# NG2092_SD_Card.net
KiCad netlist of a schematic drawn in Altium Designer
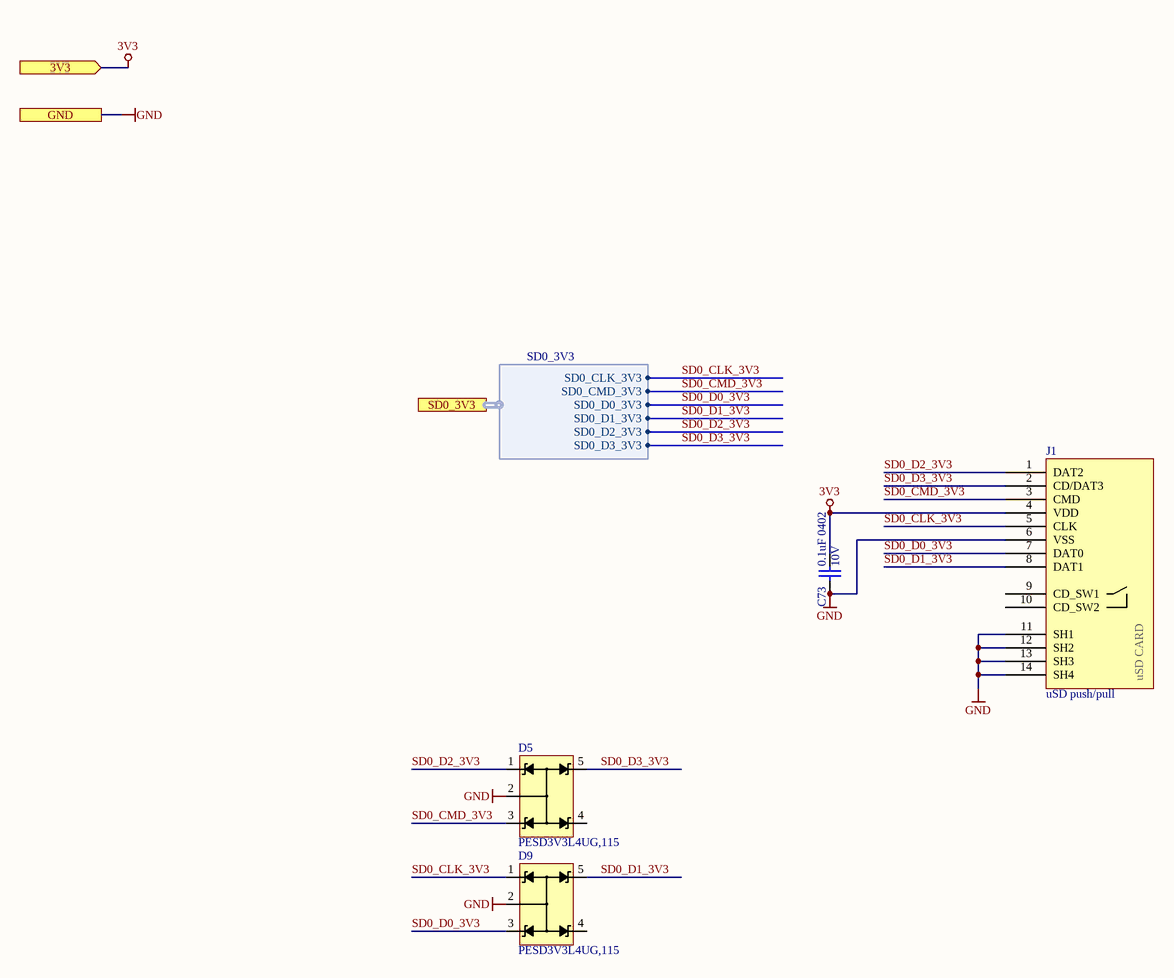
[diagram p0: NG2092_SD_Card.SchDoc]

(export (version "E")
  (design (tool "Eeschema 10.0.6"))
  (components
    (comp (ref "C73")
      (value "0.1uF 0402")
      (footprint "CAP_Altium_Vault_Generic:CAPC0402(1005)70_L")
      (description "CAP CER 0.1UF 10V X7R 0402 5%")
      (fields (field (name "TOLERANCE") "5%") (field (name "VOLTAGE RATING") "10V"))
      (libsource (lib "LuxonisMaster") (part "GRM155R71A104JA01D"))
    )
    (comp (ref "D5")
      (value "PESD3V3L4UG,115")
      (footprint "PESD3V3L4UG,115")
      (description "TVS DIODE 3V3 8V 5TSSOP")
      (libsource (lib "NG2092") (part "PESD3V3L4UG,115"))
    )
    (comp (ref "D9")
      (value "PESD3V3L4UG,115")
      (footprint "PESD3V3L4UG,115")
      (description "TVS DIODE 3V3 8V 5TSSOP")
      (libsource (lib "NG2092") (part "PESD3V3L4UG,115"))
    )
    (comp (ref "J1")
      (value "uSD push/pull")
      (footprint "LuxonisMaster:104031-0811")
      (description "CONN MICRO SD CARD PUSH-PULL R/A")
      (libsource (lib "LuxonisMaster") (part "104031-0811"))
    )
  )
  (nets
    (net (code "2") (name "/SD0_CLK_3V3") (class "Default")
      (node (ref "D9") (pin "1") (pinfunction "1_1") (pintype "passive"))
      (node (ref "J1") (pin "5") (pinfunction "CLK_5") (pintype "passive"))
    )
    (net (code "3") (name "/SD0_CMD_3V3") (class "Default")
      (node (ref "D5") (pin "3") (pinfunction "3_3") (pintype "passive"))
      (node (ref "J1") (pin "3") (pinfunction "CMD_3") (pintype "passive"))
    )
    (net (code "4") (name "/SD0_D0_3V3") (class "Default")
      (node (ref "D9") (pin "3") (pinfunction "3_3") (pintype "passive"))
      (node (ref "J1") (pin "7") (pinfunction "DAT0_7") (pintype "passive"))
    )
    (net (code "5") (name "/SD0_D1_3V3") (class "Default")
      (node (ref "D9") (pin "5") (pinfunction "5_5") (pintype "passive"))
      (node (ref "J1") (pin "8") (pinfunction "DAT1_8") (pintype "passive"))
    )
    (net (code "6") (name "/SD0_D2_3V3") (class "Default")
      (node (ref "D5") (pin "1") (pinfunction "1_1") (pintype "passive"))
      (node (ref "J1") (pin "1") (pinfunction "DAT2_1") (pintype "passive"))
    )
    (net (code "7") (name "/SD0_D3_3V3") (class "Default")
      (node (ref "D5") (pin "5") (pinfunction "5_5") (pintype "passive"))
      (node (ref "J1") (pin "2") (pinfunction "CD/DAT3_2") (pintype "passive"))
    )
    (net (code "9") (name "3V3") (class "Default")
      (node (ref "C73") (pin "2") (pinfunction "2_2") (pintype "passive"))
      (node (ref "J1") (pin "4") (pinfunction "VDD_4") (pintype "passive"))
    )
    (net (code "10") (name "GND") (class "Default")
      (node (ref "C73") (pin "1") (pinfunction "1_1") (pintype "passive"))
      (node (ref "D5") (pin "2") (pinfunction "2_2") (pintype "passive"))
      (node (ref "D9") (pin "2") (pinfunction "2_2") (pintype "passive"))
      (node (ref "J1") (pin "11") (pinfunction "SH1_11") (pintype "passive"))
      (node (ref "J1") (pin "12") (pinfunction "SH2_12") (pintype "passive"))
      (node (ref "J1") (pin "13") (pinfunction "SH3_13") (pintype "passive"))
      (node (ref "J1") (pin "14") (pinfunction "SH4_14") (pintype "passive"))
      (node (ref "J1") (pin "6") (pinfunction "VSS_6") (pintype "passive"))
    )
    (net (code "11") (name "unconnected-(D5-Pad4)") (class "Default")
      (node (ref "D5") (pin "4") (pinfunction "4_4") (pintype "passive"))
    )
    (net (code "12") (name "unconnected-(D9-Pad4)") (class "Default")
      (node (ref "D9") (pin "4") (pinfunction "4_4") (pintype "passive"))
    )
    (net (code "13") (name "unconnected-(J1-CD_SW1-Pad9)") (class "Default")
      (node (ref "J1") (pin "9") (pinfunction "CD_SW1_9") (pintype "passive"))
    )
    (net (code "14") (name "unconnected-(J1-CD_SW2-Pad10)") (class "Default")
      (node (ref "J1") (pin "10") (pinfunction "CD_SW2_10") (pintype "passive"))
    )
  )
)
